# USB_UART.net
KiCad netlist of a schematic drawn in Altium Designer
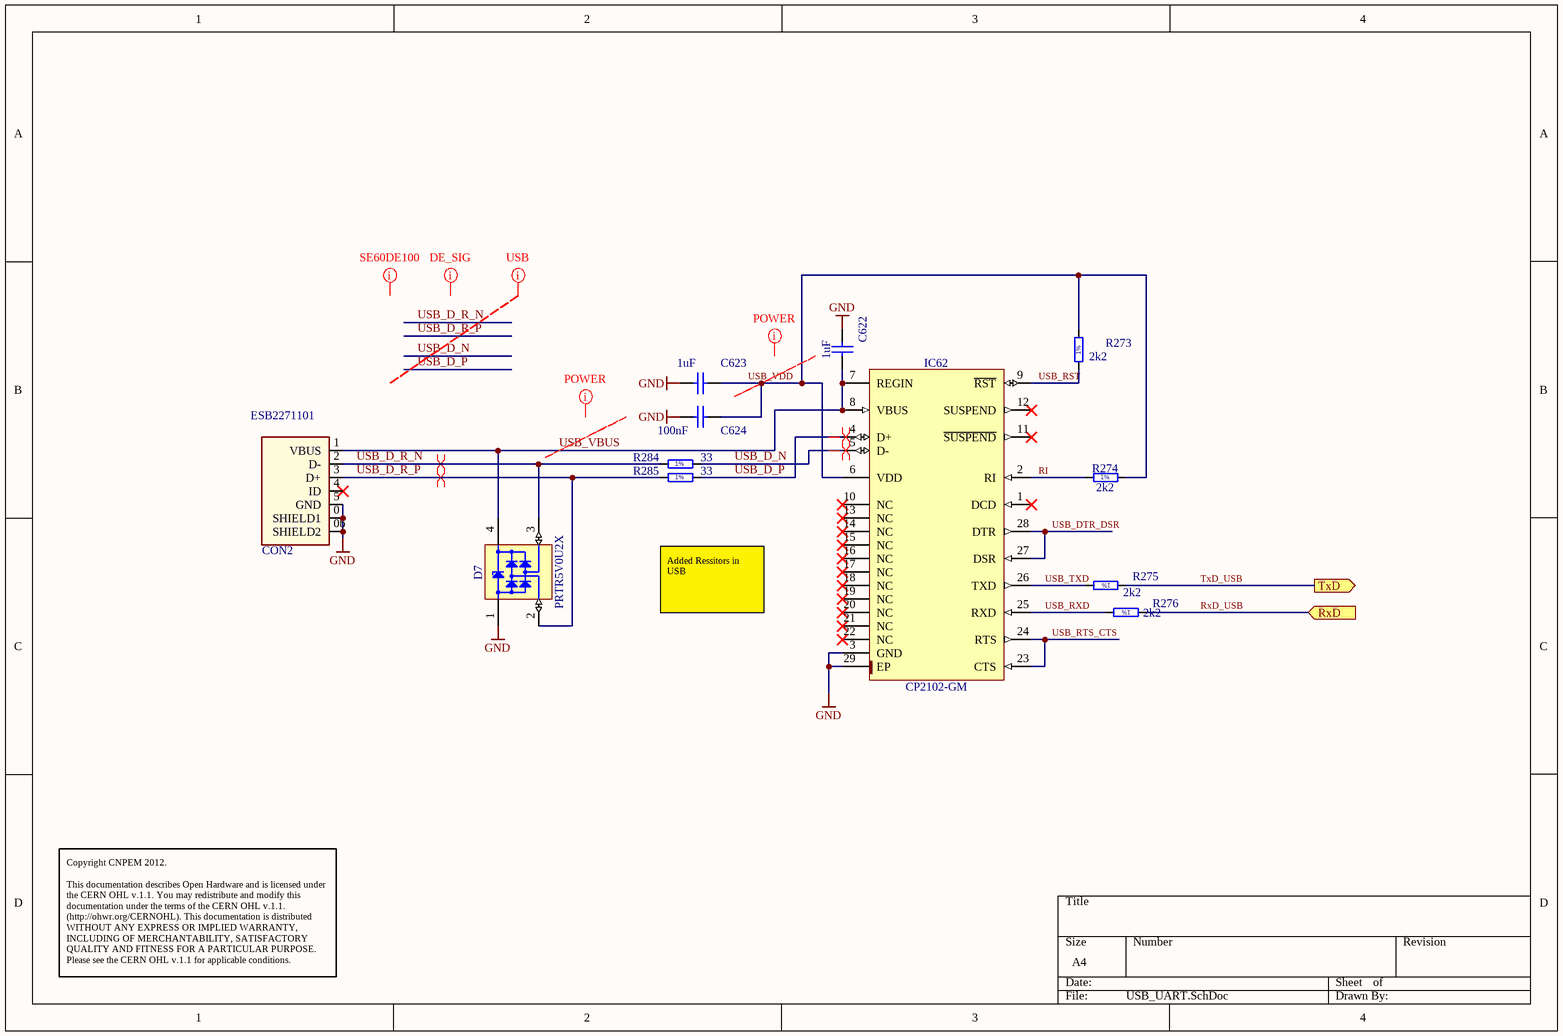
[diagram p0: USB_UART.SchDoc]

(export (version "E")
  (design (tool "Eeschema 10.0.6"))
  (components
    (comp (ref "C622")
      (value "1uF")
      (footprint "CAPC1608X87N")
      (description "Non-polarised capacitor")
      (fields
        (field (name "PART NUMBER") "CC0603_1UF_16V_10%_X7R")
        (field (name "VOLTAGE") "16V")
        (field (name "AUTHOR") "CERN DEM JLC")
      )
      (libsource (lib "Capacitors") (part "Capacitor - non polarized"))
    )
    (comp (ref "C623")
      (value "1uF")
      (footprint "CAPC1608X87N")
      (description "Non-polarised capacitor")
      (fields
        (field (name "PART NUMBER") "CC0603_1UF_16V_10%_X7R")
        (field (name "VOLTAGE") "16V")
        (field (name "AUTHOR") "CERN DEM JLC")
      )
      (libsource (lib "Capacitors") (part "Capacitor - non polarized"))
    )
    (comp (ref "C624")
      (value "100nF")
      (footprint "CAPC0603X33N")
      (description "Non-polarised capacitor")
      (fields
        (field (name "PART NUMBER") "CC0201_100NF_6.3V_10%_X5R")
        (field (name "VOLTAGE") "6.3V")
        (field (name "AUTHOR") "CERN DEM JLC")
      )
      (libsource (lib "Capacitors") (part "Capacitor - non polarized"))
    )
    (comp (ref "CON2")
      (value "ESB2271101")
      (footprint "USB_MICRO_ESB2271101")
      (description "USB micro AB connector")
      (fields (field (name "PART NUMBER") "10133"))
      (libsource (lib "LIBRARY_SCH") (part "CON_USB_AB_MICRO"))
    )
    (comp (ref "D7")
      (value "PRTR5V0U2X")
      (footprint "SOT190P230X110-4N")
      (description "Ultra Low Capacitance Double Rail-to-Rail ESD Protection Diode")
      (fields
        (field (name "VOLTAGE") "5.5V")
        (field (name "MANUFACTURER") "NXP SEMICONDUCTORS")
        (field (name "AUTHOR") "CERN DEM JLC")
      )
      (libsource (lib "ICs And Semiconductors") (part "PRTR5V0U2X"))
    )
    (comp (ref "IC62")
      (value "CP2102-GM")
      (footprint "QFN50P500X500X100-29N-S335")
      (description "Single-Chip USB to UART Bridge")
      (fields (field (name "MANUFACTURER") "SILICON LABS") (field (name "AUTHOR") "CERN DEM JLC"))
      (libsource (lib "ICs And Semiconductors") (part "CP2102-GM"))
    )
    (comp (ref "R273")
      (value "2k2")
      (footprint "RESC1005X40N")
      (description "Resistor - 1%")
      (fields
        (field (name "PART NUMBER") "R0402_2K2_1%_0.0625W_100PPM")
        (field (name "POWER") "0.0625W")
        (field (name "AUTHOR") "CERN DEM JLC")
      )
      (libsource (lib "Resistors") (part "Resistor - 1%"))
    )
    (comp (ref "R274")
      (value "2k2")
      (footprint "RESC1005X40N")
      (description "Resistor - 1%")
      (fields
        (field (name "PART NUMBER") "R0402_2K2_1%_0.0625W_100PPM")
        (field (name "POWER") "0.0625W")
        (field (name "AUTHOR") "CERN DEM JLC")
      )
      (libsource (lib "Resistors") (part "Resistor - 1%"))
    )
    (comp (ref "R275")
      (value "2k2")
      (footprint "RESC1005X40N")
      (description "Resistor - 1%")
      (fields
        (field (name "PART NUMBER") "R0402_2K2_1%_0.0625W_100PPM")
        (field (name "POWER") "0.0625W")
        (field (name "AUTHOR") "CERN DEM JLC")
      )
      (libsource (lib "Resistors") (part "Resistor - 1%"))
    )
    (comp (ref "R276")
      (value "2k2")
      (footprint "RESC1005X40N")
      (description "Resistor - 1%")
      (fields
        (field (name "PART NUMBER") "R0402_2K2_1%_0.0625W_100PPM")
        (field (name "POWER") "0.0625W")
        (field (name "AUTHOR") "CERN DEM JLC")
      )
      (libsource (lib "Resistors") (part "Resistor - 1%"))
    )
    (comp (ref "R284")
      (value "33")
      (footprint "RESC1005X40N")
      (description "Resistor - 1%")
      (fields
        (field (name "PART NUMBER") "R0402_33R_1%_0.0625W_100PPM")
        (field (name "POWER") "0.0625W")
        (field (name "AUTHOR") "CERN DEM JLC")
      )
      (libsource (lib "Resistors") (part "Resistor - 1%"))
    )
    (comp (ref "R285")
      (value "33")
      (footprint "RESC1005X40N")
      (description "Resistor - 1%")
      (fields
        (field (name "PART NUMBER") "R0402_33R_1%_0.0625W_100PPM")
        (field (name "POWER") "0.0625W")
        (field (name "AUTHOR") "CERN DEM JLC")
      )
      (libsource (lib "Resistors") (part "Resistor - 1%"))
    )
  )
  (nets
    (net (code "1") (name "/RI") (class "Default")
      (node (ref "IC62") (pin "2") (pinfunction "RI_2") (pintype "input"))
      (node (ref "R274") (pin "1") (pinfunction "1_1") (pintype "passive"))
    )
    (net (code "2") (name "/RxD_USB") (class "Default")
      (node (ref "R276") (pin "1") (pinfunction "1_1") (pintype "passive"))
    )
    (net (code "3") (name "/TxD_USB") (class "Default")
      (node (ref "R275") (pin "1") (pinfunction "1_1") (pintype "passive"))
    )
    (net (code "4") (name "/USB_DTR_DSR") (class "Default")
      (node (ref "IC62") (pin "27") (pinfunction "DSR_27") (pintype "input"))
      (node (ref "IC62") (pin "28") (pinfunction "DTR_28") (pintype "output"))
    )
    (net (code "5") (name "/USB_D_N") (class "Default")
      (node (ref "IC62") (pin "5") (pinfunction "D-_5") (pintype "bidirectional"))
      (node (ref "R284") (pin "2") (pinfunction "2_2") (pintype "passive"))
    )
    (net (code "6") (name "/USB_D_P") (class "Default")
      (node (ref "IC62") (pin "4") (pinfunction "D+_4") (pintype "bidirectional"))
      (node (ref "R285") (pin "2") (pinfunction "2_2") (pintype "passive"))
    )
    (net (code "7") (name "/USB_D_R_N") (class "Default")
      (node (ref "CON2") (pin "2") (pinfunction "D-_2") (pintype "passive"))
      (node (ref "D7") (pin "3") (pinfunction "I/O2_3") (pintype "bidirectional"))
      (node (ref "R284") (pin "1") (pinfunction "1_1") (pintype "passive"))
    )
    (net (code "8") (name "/USB_D_R_P") (class "Default")
      (node (ref "CON2") (pin "3") (pinfunction "D+_3") (pintype "passive"))
      (node (ref "D7") (pin "2") (pinfunction "I/O1_2") (pintype "bidirectional"))
      (node (ref "R285") (pin "1") (pinfunction "1_1") (pintype "passive"))
    )
    (net (code "9") (name "/USB_RST") (class "Default")
      (node (ref "IC62") (pin "9") (pinfunction "~{RST}_9") (pintype "bidirectional"))
      (node (ref "R273") (pin "1") (pinfunction "1_1") (pintype "passive"))
    )
    (net (code "10") (name "/USB_RTS_CTS") (class "Default")
      (node (ref "IC62") (pin "23") (pinfunction "CTS_23") (pintype "input"))
      (node (ref "IC62") (pin "24") (pinfunction "RTS_24") (pintype "output"))
    )
    (net (code "11") (name "/USB_RXD") (class "Default")
      (node (ref "IC62") (pin "25") (pinfunction "RXD_25") (pintype "input"))
      (node (ref "R276") (pin "2") (pinfunction "2_2") (pintype "passive"))
    )
    (net (code "12") (name "/USB_TXD") (class "Default")
      (node (ref "IC62") (pin "26") (pinfunction "TXD_26") (pintype "output"))
      (node (ref "R275") (pin "2") (pinfunction "2_2") (pintype "passive"))
    )
    (net (code "13") (name "/USB_VBUS") (class "Default")
      (node (ref "C622") (pin "2") (pinfunction "2_2") (pintype "passive"))
      (node (ref "CON2") (pin "1") (pinfunction "VBUS_1") (pintype "passive"))
      (node (ref "D7") (pin "4") (pinfunction "VCC_4") (pintype "power_in"))
      (node (ref "IC62") (pin "7") (pinfunction "REGIN_7") (pintype "power_in"))
      (node (ref "IC62") (pin "8") (pinfunction "VBUS_8") (pintype "input"))
    )
    (net (code "14") (name "/USB_VDD") (class "Default")
      (node (ref "C623") (pin "2") (pinfunction "2_2") (pintype "passive"))
      (node (ref "C624") (pin "2") (pinfunction "2_2") (pintype "passive"))
      (node (ref "IC62") (pin "6") (pinfunction "VDD_6") (pintype "power_in"))
      (node (ref "R273") (pin "2") (pinfunction "2_2") (pintype "passive"))
      (node (ref "R274") (pin "2") (pinfunction "2_2") (pintype "passive"))
    )
    (net (code "15") (name "GND") (class "Default")
      (node (ref "C622") (pin "1") (pinfunction "1_1") (pintype "passive"))
      (node (ref "C623") (pin "1") (pinfunction "1_1") (pintype "passive"))
      (node (ref "C624") (pin "1") (pinfunction "1_1") (pintype "passive"))
      (node (ref "CON2") (pin "0") (pinfunction "SHIELD1_0") (pintype "passive"))
      (node (ref "CON2") (pin "0a") (pinfunction "SHIELD1_0a") (pintype "passive"))
      (node (ref "CON2") (pin "0b") (pinfunction "SHIELD2_0b") (pintype "passive"))
      (node (ref "CON2") (pin "0c") (pinfunction "SHIELD2_0c") (pintype "passive"))
      (node (ref "CON2") (pin "5") (pinfunction "GND_5") (pintype "passive"))
      (node (ref "D7") (pin "1") (pinfunction "GND_1") (pintype "power_in"))
      (node (ref "IC62") (pin "29") (pinfunction "EP_29") (pintype "power_in"))
      (node (ref "IC62") (pin "3") (pinfunction "GND_3") (pintype "power_in"))
    )
    (net (code "16") (name "unconnected-(CON2-ID-Pad4)") (class "Default")
      (node (ref "CON2") (pin "4") (pinfunction "ID_4") (pintype "passive+no_connect"))
    )
    (net (code "17") (name "unconnected-(IC62-DCD-Pad1)") (class "Default")
      (node (ref "IC62") (pin "1") (pinfunction "DCD_1") (pintype "input+no_connect"))
    )
    (net (code "18") (name "unconnected-(IC62-NC-Pad10)") (class "Default")
      (node (ref "IC62") (pin "10") (pinfunction "NC_10") (pintype "passive+no_connect"))
    )
    (net (code "19") (name "unconnected-(IC62-NC-Pad13)") (class "Default")
      (node (ref "IC62") (pin "13") (pinfunction "NC_13") (pintype "passive+no_connect"))
    )
    (net (code "20") (name "unconnected-(IC62-NC-Pad14)") (class "Default")
      (node (ref "IC62") (pin "14") (pinfunction "NC_14") (pintype "passive+no_connect"))
    )
    (net (code "21") (name "unconnected-(IC62-NC-Pad15)") (class "Default")
      (node (ref "IC62") (pin "15") (pinfunction "NC_15") (pintype "passive+no_connect"))
    )
    (net (code "22") (name "unconnected-(IC62-NC-Pad16)") (class "Default")
      (node (ref "IC62") (pin "16") (pinfunction "NC_16") (pintype "passive+no_connect"))
    )
    (net (code "23") (name "unconnected-(IC62-NC-Pad17)") (class "Default")
      (node (ref "IC62") (pin "17") (pinfunction "NC_17") (pintype "passive+no_connect"))
    )
    (net (code "24") (name "unconnected-(IC62-NC-Pad18)") (class "Default")
      (node (ref "IC62") (pin "18") (pinfunction "NC_18") (pintype "passive+no_connect"))
    )
    (net (code "25") (name "unconnected-(IC62-NC-Pad19)") (class "Default")
      (node (ref "IC62") (pin "19") (pinfunction "NC_19") (pintype "passive+no_connect"))
    )
    (net (code "26") (name "unconnected-(IC62-NC-Pad20)") (class "Default")
      (node (ref "IC62") (pin "20") (pinfunction "NC_20") (pintype "passive+no_connect"))
    )
    (net (code "27") (name "unconnected-(IC62-NC-Pad21)") (class "Default")
      (node (ref "IC62") (pin "21") (pinfunction "NC_21") (pintype "passive+no_connect"))
    )
    (net (code "28") (name "unconnected-(IC62-NC-Pad22)") (class "Default")
      (node (ref "IC62") (pin "22") (pinfunction "NC_22") (pintype "passive+no_connect"))
    )
    (net (code "29") (name "unconnected-(IC62-SUSPEND-Pad12)") (class "Default")
      (node (ref "IC62") (pin "12") (pinfunction "SUSPEND_12") (pintype "output+no_connect"))
    )
    (net (code "30") (name "unconnected-(IC62-~{SUSPEND}-Pad11)") (class "Default")
      (node (ref "IC62") (pin "11") (pinfunction "~{SUSPEND}_11") (pintype "output+no_connect"))
    )
  )
)
